# Controller_Board_Interface.net
KiCad netlist of a schematic drawn in Altium Designer
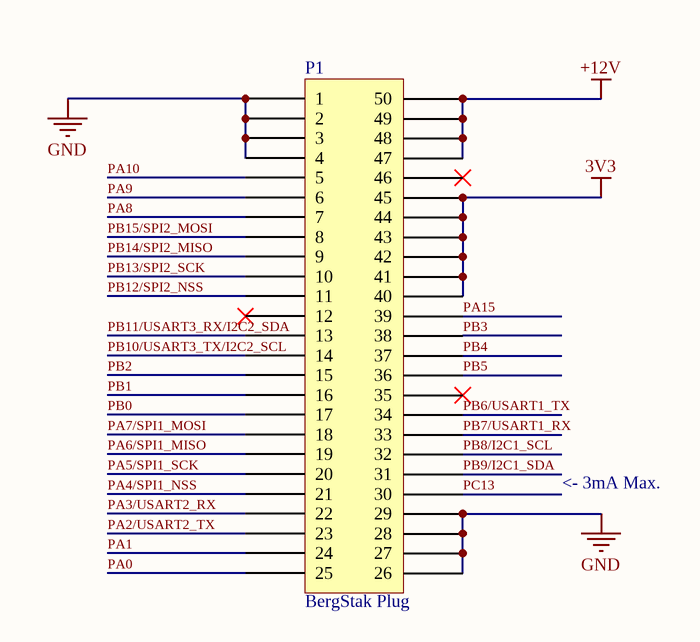
[diagram p0: Controller_Board_Interface.SchDoc]

(export (version "E")
  (design (tool "Eeschema 10.0.6"))
  (components
    (comp (ref "P1")
      (value "BergStak Plug")
      (footprint "Bergstak 50 Pos Plug")
      (description "50 Position Connector Plug, Outer Shroud Contacts Surface Mount Gold")
      (libsource (lib "Midnight Sun Integrated Library") (part "BergStak 50 Position Connector Plug"))
    )
  )
  (nets
    (net (code "1") (name "+12V") (class "Default")
      (node (ref "P1") (pin "47") (pinfunction "47_47") (pintype "passive"))
      (node (ref "P1") (pin "48") (pinfunction "48_48") (pintype "passive"))
      (node (ref "P1") (pin "49") (pinfunction "49_49") (pintype "passive"))
      (node (ref "P1") (pin "50") (pinfunction "50_50") (pintype "passive"))
    )
    (net (code "2") (name "/PA0") (class "Default")
      (node (ref "P1") (pin "25") (pinfunction "25_25") (pintype "passive"))
    )
    (net (code "3") (name "/PA1") (class "Default")
      (node (ref "P1") (pin "24") (pinfunction "24_24") (pintype "passive"))
    )
    (net (code "4") (name "/PA2{slash}USART2_TX") (class "Default")
      (node (ref "P1") (pin "23") (pinfunction "23_23") (pintype "passive"))
    )
    (net (code "5") (name "/PA3{slash}USART2_RX") (class "Default")
      (node (ref "P1") (pin "22") (pinfunction "22_22") (pintype "passive"))
    )
    (net (code "6") (name "/PA4{slash}SPI1_NSS") (class "Default")
      (node (ref "P1") (pin "21") (pinfunction "21_21") (pintype "passive"))
    )
    (net (code "7") (name "/PA5{slash}SPI1_SCK") (class "Default")
      (node (ref "P1") (pin "20") (pinfunction "20_20") (pintype "passive"))
    )
    (net (code "8") (name "/PA6{slash}SPI1_MISO") (class "Default")
      (node (ref "P1") (pin "19") (pinfunction "19_19") (pintype "passive"))
    )
    (net (code "9") (name "/PA7{slash}SPI1_MOSI") (class "Default")
      (node (ref "P1") (pin "18") (pinfunction "18_18") (pintype "passive"))
    )
    (net (code "10") (name "/PA8") (class "Default")
      (node (ref "P1") (pin "7") (pinfunction "7_7") (pintype "passive"))
    )
    (net (code "11") (name "/PA9") (class "Default")
      (node (ref "P1") (pin "6") (pinfunction "6_6") (pintype "passive"))
    )
    (net (code "12") (name "/PA10") (class "Default")
      (node (ref "P1") (pin "5") (pinfunction "5_5") (pintype "passive"))
    )
    (net (code "13") (name "/PA15") (class "Default")
      (node (ref "P1") (pin "39") (pinfunction "39_39") (pintype "passive"))
    )
    (net (code "14") (name "/PB0") (class "Default")
      (node (ref "P1") (pin "17") (pinfunction "17_17") (pintype "passive"))
    )
    (net (code "15") (name "/PB1") (class "Default")
      (node (ref "P1") (pin "16") (pinfunction "16_16") (pintype "passive"))
    )
    (net (code "16") (name "/PB2") (class "Default")
      (node (ref "P1") (pin "15") (pinfunction "15_15") (pintype "passive"))
    )
    (net (code "17") (name "/PB3") (class "Default")
      (node (ref "P1") (pin "38") (pinfunction "38_38") (pintype "passive"))
    )
    (net (code "18") (name "/PB4") (class "Default")
      (node (ref "P1") (pin "37") (pinfunction "37_37") (pintype "passive"))
    )
    (net (code "19") (name "/PB5") (class "Default")
      (node (ref "P1") (pin "36") (pinfunction "36_36") (pintype "passive"))
    )
    (net (code "20") (name "/PB6{slash}USART1_TX") (class "Default")
      (node (ref "P1") (pin "34") (pinfunction "34_34") (pintype "passive"))
    )
    (net (code "21") (name "/PB7{slash}USART1_RX") (class "Default")
      (node (ref "P1") (pin "33") (pinfunction "33_33") (pintype "passive"))
    )
    (net (code "22") (name "/PB8{slash}I2C1_SCL") (class "Default")
      (node (ref "P1") (pin "32") (pinfunction "32_32") (pintype "passive"))
    )
    (net (code "23") (name "/PB9{slash}I2C1_SDA") (class "Default")
      (node (ref "P1") (pin "31") (pinfunction "31_31") (pintype "passive"))
    )
    (net (code "24") (name "/PB10{slash}USART3_TX{slash}I2C2_SCL") (class "Default")
      (node (ref "P1") (pin "14") (pinfunction "14_14") (pintype "passive"))
    )
    (net (code "25") (name "/PB11{slash}USART3_RX{slash}I2C2_SDA") (class "Default")
      (node (ref "P1") (pin "13") (pinfunction "13_13") (pintype "passive"))
    )
    (net (code "26") (name "/PB12{slash}SPI2_NSS") (class "Default")
      (node (ref "P1") (pin "11") (pinfunction "11_11") (pintype "passive"))
    )
    (net (code "27") (name "/PB13{slash}SPI2_SCK") (class "Default")
      (node (ref "P1") (pin "10") (pinfunction "10_10") (pintype "passive"))
    )
    (net (code "28") (name "/PB14{slash}SPI2_MISO") (class "Default")
      (node (ref "P1") (pin "9") (pinfunction "9_9") (pintype "passive"))
    )
    (net (code "29") (name "/PB15{slash}SPI2_MOSI") (class "Default")
      (node (ref "P1") (pin "8") (pinfunction "8_8") (pintype "passive"))
    )
    (net (code "30") (name "/PC13") (class "Default")
      (node (ref "P1") (pin "30") (pinfunction "30_30") (pintype "passive"))
    )
    (net (code "31") (name "3V3") (class "Default")
      (node (ref "P1") (pin "40") (pinfunction "40_40") (pintype "passive"))
      (node (ref "P1") (pin "41") (pinfunction "41_41") (pintype "passive"))
      (node (ref "P1") (pin "42") (pinfunction "42_42") (pintype "passive"))
      (node (ref "P1") (pin "43") (pinfunction "43_43") (pintype "passive"))
      (node (ref "P1") (pin "44") (pinfunction "44_44") (pintype "passive"))
      (node (ref "P1") (pin "45") (pinfunction "45_45") (pintype "passive"))
    )
    (net (code "32") (name "GND") (class "Default")
      (node (ref "P1") (pin "1") (pinfunction "1_1") (pintype "passive"))
      (node (ref "P1") (pin "2") (pinfunction "2_2") (pintype "passive"))
      (node (ref "P1") (pin "26") (pinfunction "26_26") (pintype "passive"))
      (node (ref "P1") (pin "27") (pinfunction "27_27") (pintype "passive"))
      (node (ref "P1") (pin "28") (pinfunction "28_28") (pintype "passive"))
      (node (ref "P1") (pin "29") (pinfunction "29_29") (pintype "passive"))
      (node (ref "P1") (pin "3") (pinfunction "3_3") (pintype "passive"))
      (node (ref "P1") (pin "4") (pinfunction "4_4") (pintype "passive"))
    )
    (net (code "33") (name "unconnected-(P1-Pad12)") (class "Default")
      (node (ref "P1") (pin "12") (pinfunction "12_12") (pintype "passive+no_connect"))
    )
    (net (code "34") (name "unconnected-(P1-Pad35)") (class "Default")
      (node (ref "P1") (pin "35") (pinfunction "35_35") (pintype "passive+no_connect"))
    )
    (net (code "35") (name "unconnected-(P1-Pad46)") (class "Default")
      (node (ref "P1") (pin "46") (pinfunction "46_46") (pintype "passive+no_connect"))
    )
  )
)
